# main.net
KiCad netlist of a schematic drawn in Altium Designer
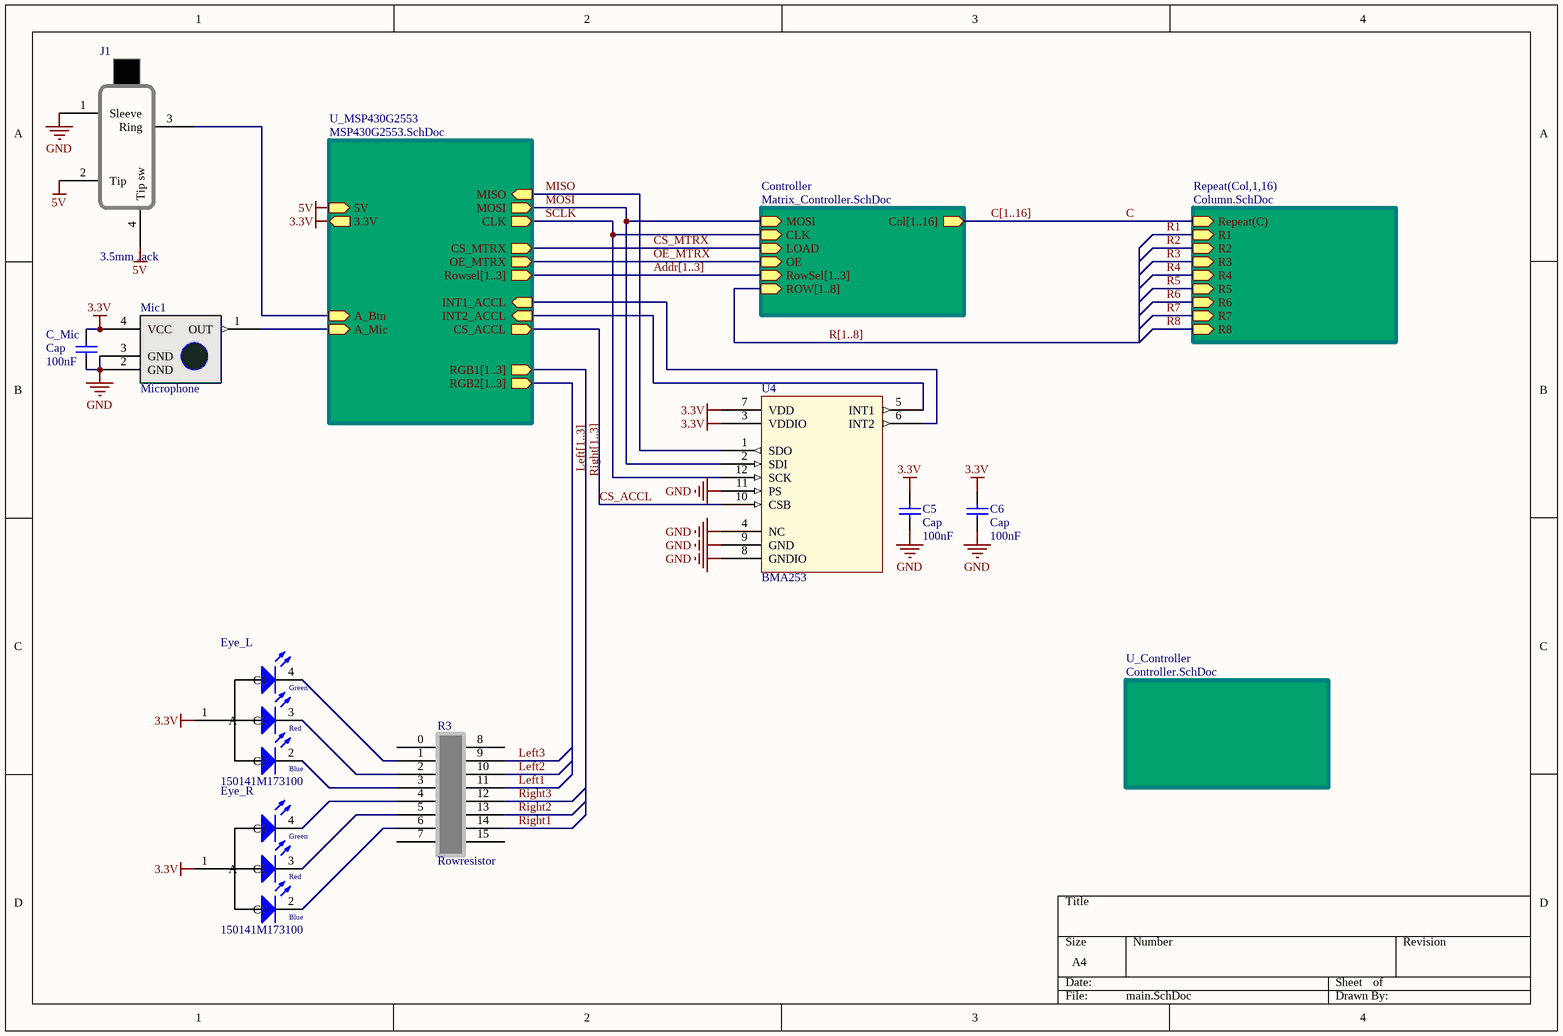
[diagram p0: main.SchDoc]

(export (version "E")
  (design (tool "Eeschema 10.0.6"))
  (components
    (comp (ref "C5")
      (value "Cap")
      (footprint "6-0805_M")
      (description "Capacitor")
      (fields (field (name "ALTIUM_VALUE") "100nF") (field (name "PUBLISHER") "Altium Limited"))
      (libsource (lib "Miscellaneous Devices") (part "Cap"))
    )
    (comp (ref "C6")
      (value "Cap")
      (footprint "6-0805_M")
      (description "Capacitor")
      (fields (field (name "ALTIUM_VALUE") "100nF") (field (name "PUBLISHER") "Altium Limited"))
      (libsource (lib "Miscellaneous Devices") (part "Cap"))
    )
    (comp (ref "C_Mic")
      (value "Cap")
      (footprint "6-0805_M")
      (description "Capacitor")
      (fields (field (name "ALTIUM_VALUE") "100nF") (field (name "PUBLISHER") "Altium Limited"))
      (libsource (lib "Miscellaneous Devices") (part "Cap"))
    )
    (comp (ref "Eye_L")
      (value "150141M173100")
      (footprint "3528_A")
      (description "SMD Full-Color Top LED, WL-SFTW, Red & Green & Blue")
      (libsource (lib "WL-SFTW SMD TOP LED full-color waterclear") (part "150141M173100"))
    )
    (comp (ref "Eye_R")
      (value "150141M173100")
      (footprint "3528_A")
      (description "SMD Full-Color Top LED, WL-SFTW, Red & Green & Blue")
      (libsource (lib "WL-SFTW SMD TOP LED full-color waterclear") (part "150141M173100"))
    )
    (comp (ref "J1")
      (value "3.5mm Jack")
      (footprint "Phonejack")
      (libsource (lib "Phonejack") (part "Phonejack"))
    )
    (comp (ref "Mic1")
      (value "Microphone")
      (footprint "SPW2430HR5H-B")
      (description "SPW2430HR5H-B  MEMs Microphone")
      (libsource (lib "SPW2430") (part "MIC"))
    )
    (comp (ref "R3")
      (value "Rowresistor")
      (footprint "Rowres")
      (description "Row resistor, 8")
      (libsource (lib "Rowres") (part "Rowres"))
    )
    (comp (ref "U4")
      (value "BMA253")
      (footprint "BMA253")
      (description "accelerometer")
      (libsource (lib "BMA253") (part "ACCELEROMETER"))
    )
  )
  (nets
    (net (code "20") (name "/A_Btn") (class "Default")
      (node (ref "J1") (pin "3") (pinfunction "Ring_3") (pintype "passive"))
    )
    (net (code "21") (name "/A_Mic") (class "Default")
      (node (ref "Mic1") (pin "1") (pinfunction "OUT_1") (pintype "output"))
    )
    (net (code "24") (name "/CS_ACCL") (class "Default")
      (node (ref "U4") (pin "10") (pinfunction "CSB_10") (pintype "input"))
    )
    (net (code "27") (name "/INT1_ACCL") (class "Default")
      (node (ref "U4") (pin "6") (pinfunction "INT2_6") (pintype "output"))
    )
    (net (code "28") (name "/INT2_ACCL") (class "Default")
      (node (ref "U4") (pin "5") (pinfunction "INT1_5") (pintype "output"))
    )
    (net (code "29") (name "/Left1") (class "Default") (node (ref "R3") (pin "11") (pintype "passive")))
    (net (code "30") (name "/Left2") (class "Default") (node (ref "R3") (pin "10") (pintype "passive")))
    (net (code "31") (name "/Left3") (class "Default") (node (ref "R3") (pin "9") (pintype "passive")))
    (net (code "33") (name "/MISO") (class "Default")
      (node (ref "U4") (pin "1") (pinfunction "SDO_1") (pintype "output"))
    )
    (net (code "34") (name "/MOSI") (class "Default")
      (node (ref "U4") (pin "2") (pinfunction "SDI_2") (pintype "input"))
    )
    (net (code "45") (name "/Right1") (class "Default") (node (ref "R3") (pin "14") (pintype "passive")))
    (net (code "46") (name "/Right2") (class "Default") (node (ref "R3") (pin "13") (pintype "passive")))
    (net (code "47") (name "/Right3") (class "Default") (node (ref "R3") (pin "12") (pintype "passive")))
    (net (code "49") (name "/SCLK") (class "Default")
      (node (ref "U4") (pin "12") (pinfunction "SCK_12") (pintype "input"))
    )
    (net (code "50") (name "3.3V") (class "Default")
      (node (ref "C5") (pin "2") (pinfunction "2_2") (pintype "passive"))
      (node (ref "C6") (pin "2") (pinfunction "2_2") (pintype "passive"))
      (node (ref "C_Mic") (pin "1") (pinfunction "1_1") (pintype "passive"))
      (node (ref "Eye_L") (pin "1") (pinfunction "A_1") (pintype "passive"))
      (node (ref "Eye_R") (pin "1") (pinfunction "A_1") (pintype "passive"))
      (node (ref "Mic1") (pin "4") (pinfunction "VCC_4") (pintype "passive"))
      (node (ref "U4") (pin "3") (pinfunction "VDDIO_3") (pintype "passive"))
      (node (ref "U4") (pin "7") (pinfunction "VDD_7") (pintype "passive"))
    )
    (net (code "51") (name "5V") (class "Default")
      (node (ref "J1") (pin "2") (pinfunction "Tip_2") (pintype "passive"))
      (node (ref "J1") (pin "4") (pinfunction "Tip_sw_4") (pintype "passive"))
    )
    (net (code "52") (name "GND") (class "Default")
      (node (ref "C5") (pin "1") (pinfunction "1_1") (pintype "passive"))
      (node (ref "C6") (pin "1") (pinfunction "1_1") (pintype "passive"))
      (node (ref "C_Mic") (pin "2") (pinfunction "2_2") (pintype "passive"))
      (node (ref "J1") (pin "1") (pinfunction "Sleeve_1") (pintype "passive"))
      (node (ref "Mic1") (pin "2") (pinfunction "GND_2") (pintype "passive"))
      (node (ref "Mic1") (pin "3") (pinfunction "GND_3") (pintype "passive"))
      (node (ref "U4") (pin "11") (pinfunction "PS_11") (pintype "input"))
      (node (ref "U4") (pin "4") (pinfunction "NC_4") (pintype "passive"))
      (node (ref "U4") (pin "8") (pinfunction "GNDIO_8") (pintype "passive"))
      (node (ref "U4") (pin "9") (pinfunction "GND_9") (pintype "passive"))
    )
    (net (code "53") (name "Net-(Eye_L-C1)") (class "Default")
      (node (ref "Eye_L") (pin "4") (pinfunction "C1_4") (pintype "passive"))
      (node (ref "R3") (pin "1") (pintype "passive"))
    )
    (net (code "54") (name "Net-(Eye_L-C2)") (class "Default")
      (node (ref "Eye_L") (pin "3") (pinfunction "C2_3") (pintype "passive"))
      (node (ref "R3") (pin "2") (pintype "passive"))
    )
    (net (code "55") (name "Net-(Eye_L-C3)") (class "Default")
      (node (ref "Eye_L") (pin "2") (pinfunction "C3_2") (pintype "passive"))
      (node (ref "R3") (pin "3") (pintype "passive"))
    )
    (net (code "56") (name "Net-(Eye_R-C1)") (class "Default")
      (node (ref "Eye_R") (pin "4") (pinfunction "C1_4") (pintype "passive"))
      (node (ref "R3") (pin "4") (pintype "passive"))
    )
    (net (code "57") (name "Net-(Eye_R-C2)") (class "Default")
      (node (ref "Eye_R") (pin "3") (pinfunction "C2_3") (pintype "passive"))
      (node (ref "R3") (pin "5") (pintype "passive"))
    )
    (net (code "58") (name "Net-(Eye_R-C3)") (class "Default")
      (node (ref "Eye_R") (pin "2") (pinfunction "C3_2") (pintype "passive"))
      (node (ref "R3") (pin "6") (pintype "passive"))
    )
    (net (code "59") (name "unconnected-(R3-Pad0)") (class "Default")
      (node (ref "R3") (pin "0") (pintype "passive"))
    )
    (net (code "60") (name "unconnected-(R3-Pad7)") (class "Default")
      (node (ref "R3") (pin "7") (pintype "passive"))
    )
    (net (code "61") (name "unconnected-(R3-Pad8)") (class "Default")
      (node (ref "R3") (pin "8") (pintype "passive"))
    )
    (net (code "62") (name "unconnected-(R3-Pad15)") (class "Default")
      (node (ref "R3") (pin "15") (pintype "passive"))
    )
  )
)
